# medulla_2026-05-03.net
KiCad netlist of a schematic drawn in EasyEDA Pro
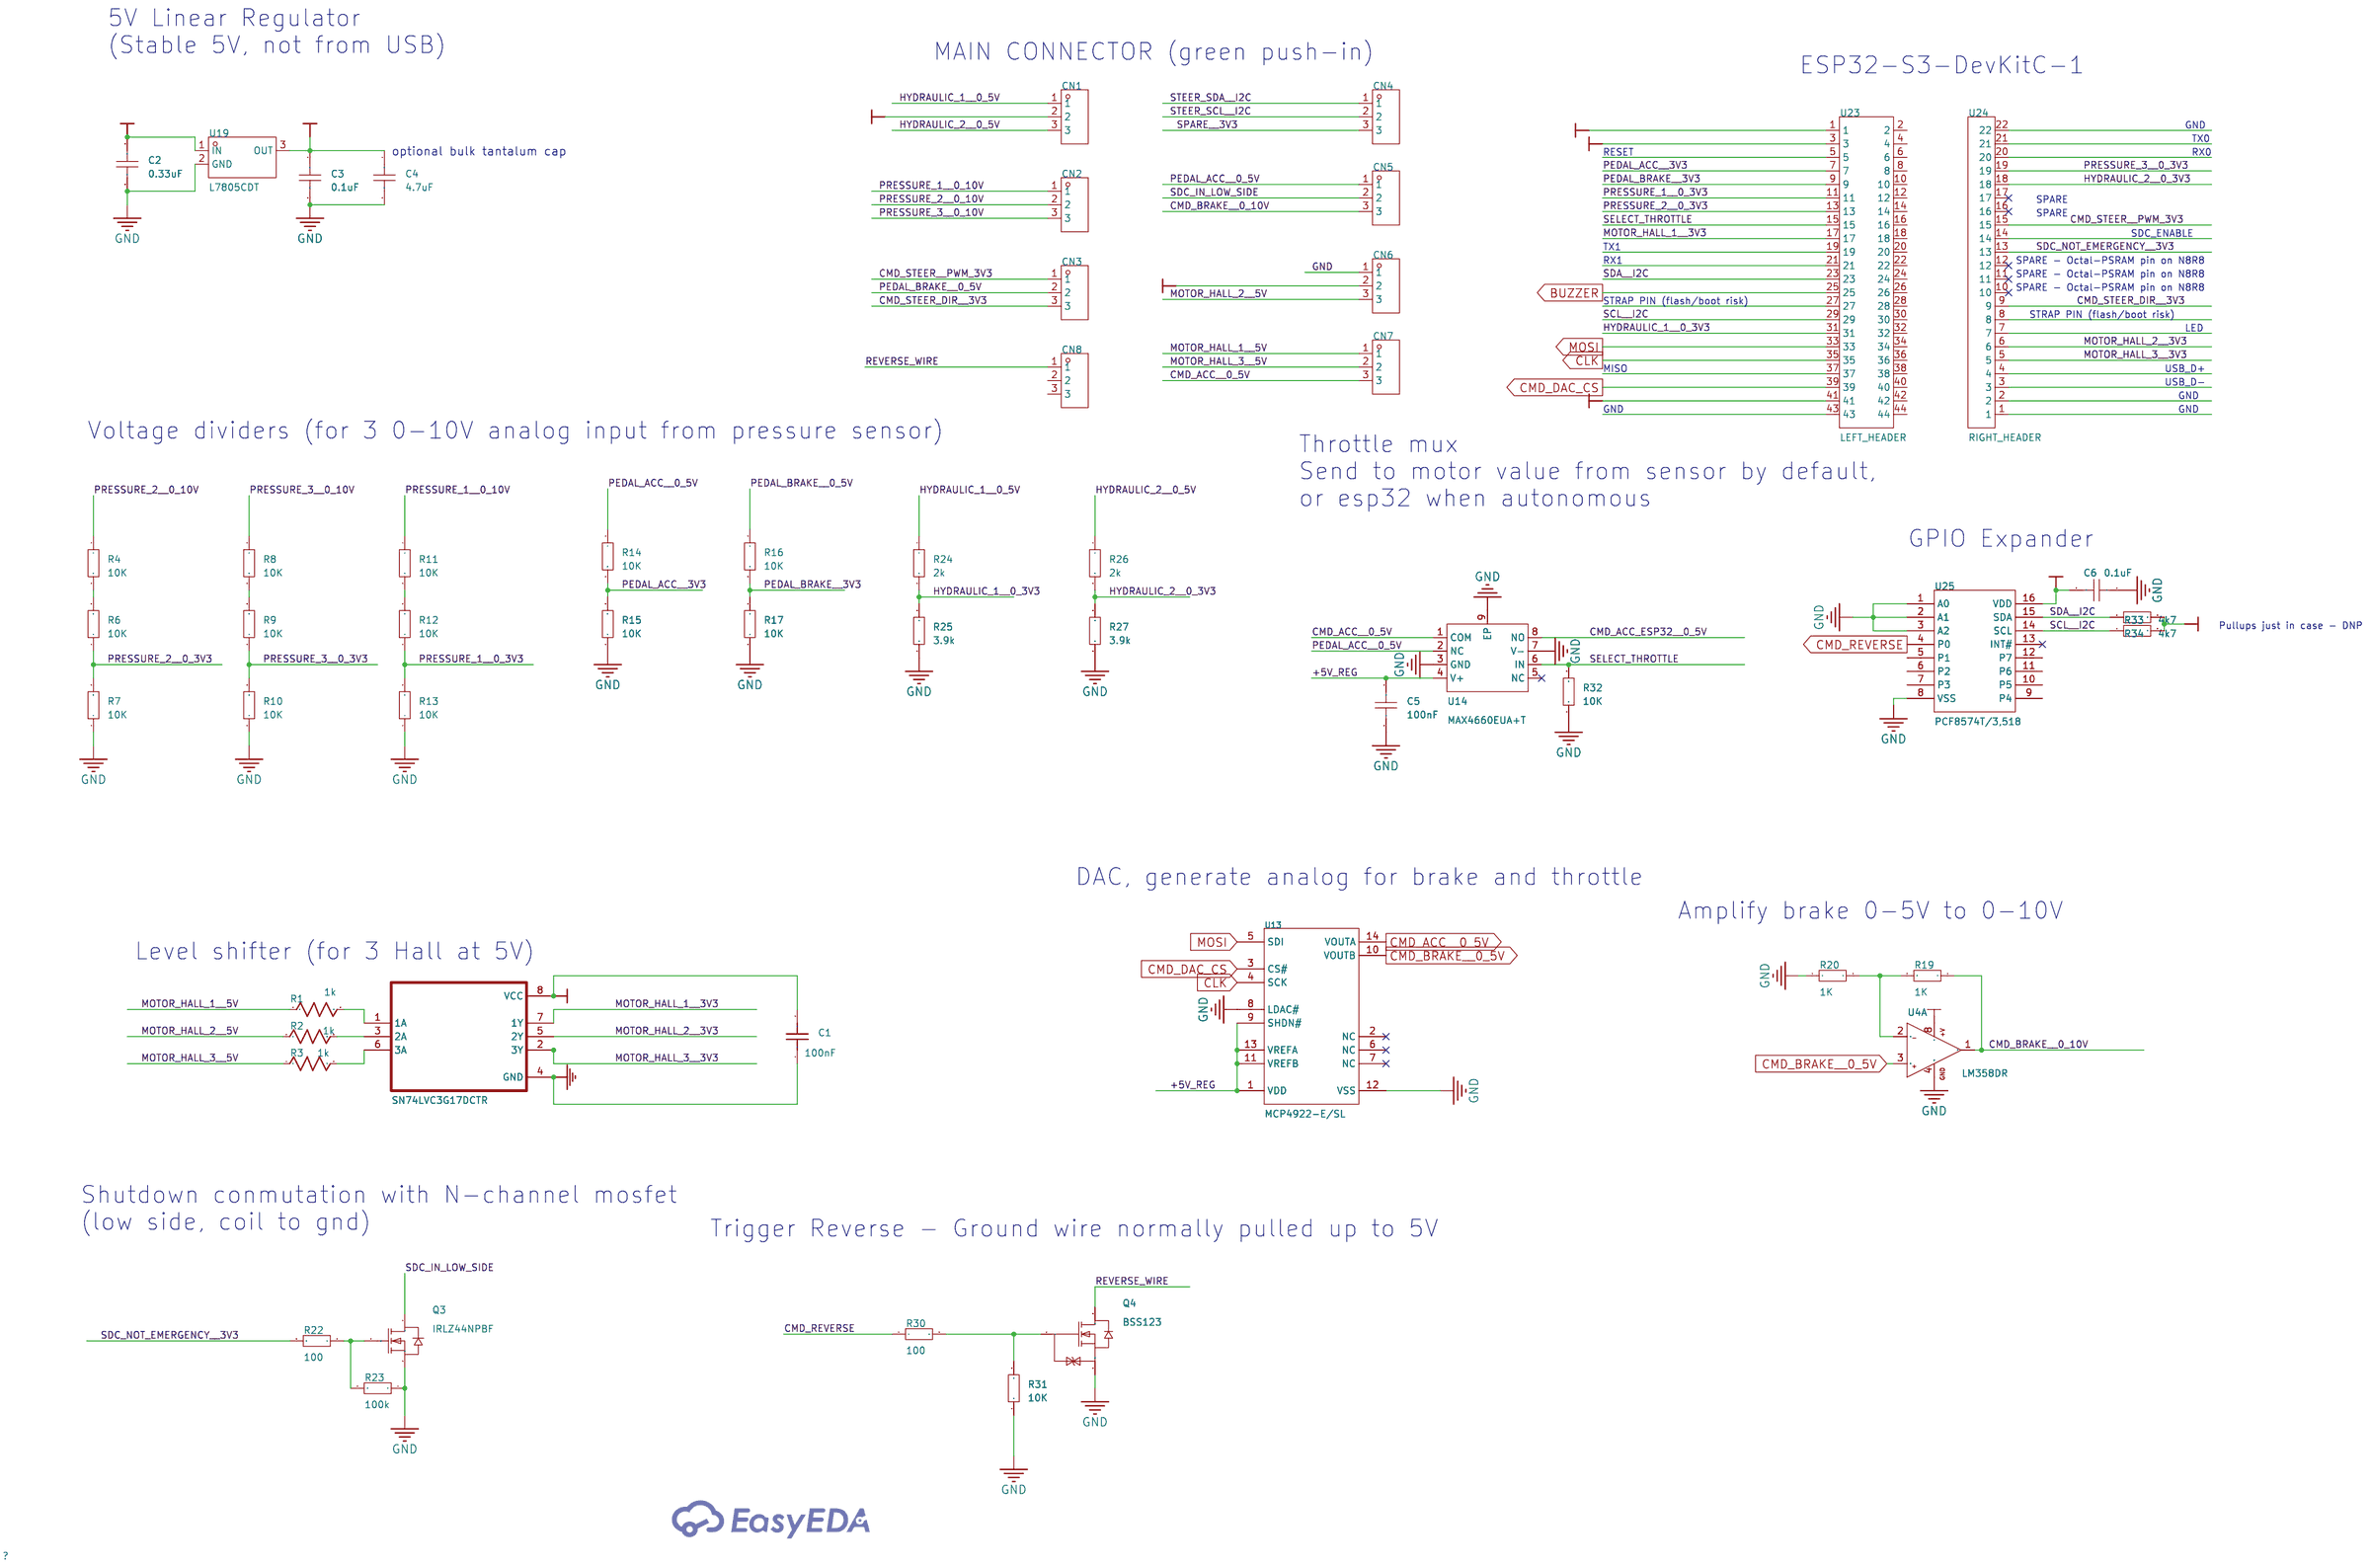
[diagram p0: schematic sheet]

(export (version "E")
  (design (tool "Eeschema 10.0.6"))
  (components
    (comp (ref "C1")
      (value "100nF")
      (footprint "easyedapro:C0603")
      (fields (field (name "Contributor") "LCEDA_Lib"))
      (libsource (lib "easyedapro") (part "100nF"))
    )
    (comp (ref "C2")
      (value "0.33uF")
      (footprint "easyedapro:C0603")
      (libsource (lib "easyedapro") (part "CAP"))
    )
    (comp (ref "C3")
      (value "0.1uF")
      (footprint "easyedapro:C0603")
      (libsource (lib "easyedapro") (part "CAP"))
    )
    (comp (ref "C4")
      (value "4.7uF")
      (footprint "easyedapro:C0603")
      (libsource (lib "easyedapro") (part "CAP"))
    )
    (comp (ref "C5")
      (value "100nF")
      (footprint "easyedapro:C0603")
      (libsource (lib "easyedapro") (part "CAP"))
    )
    (comp (ref "C6")
      (value "0.1uF")
      (footprint "easyedapro:C0603")
      (libsource (lib "easyedapro") (part "CAP"))
    )
    (comp (ref "CN1")
      (value "1990012")
      (footprint "easyedapro:CONN-TH_3P-P2.50-S5.00_1990012")
      (libsource (lib "easyedapro") (part "1990012"))
    )
    (comp (ref "CN2")
      (value "1990012")
      (footprint "easyedapro:CONN-TH_3P-P2.50-S5.00_1990012")
      (libsource (lib "easyedapro") (part "1990012"))
    )
    (comp (ref "CN3")
      (value "1990012")
      (footprint "easyedapro:CONN-TH_3P-P2.50-S5.00_1990012")
      (libsource (lib "easyedapro") (part "1990012"))
    )
    (comp (ref "CN4")
      (value "1990012")
      (footprint "easyedapro:CONN-TH_3P-P2.50-S5.00_1990012")
      (libsource (lib "easyedapro") (part "1990012"))
    )
    (comp (ref "CN5")
      (value "1990012")
      (footprint "easyedapro:CONN-TH_3P-P2.50-S5.00_1990012")
      (libsource (lib "easyedapro") (part "1990012"))
    )
    (comp (ref "CN6")
      (value "1990012")
      (footprint "easyedapro:CONN-TH_3P-P2.50-S5.00_1990012")
      (libsource (lib "easyedapro") (part "1990012"))
    )
    (comp (ref "CN7")
      (value "1990012")
      (footprint "easyedapro:CONN-TH_3P-P2.50-S5.00_1990012")
      (libsource (lib "easyedapro") (part "1990012"))
    )
    (comp (ref "CN8")
      (value "1990012")
      (footprint "easyedapro:CONN-TH_3P-P2.50-S5.00_1990012")
      (libsource (lib "easyedapro") (part "1990012"))
    )
    (comp (ref "Q3")
      (value "IRLZ44NPBF")
      (footprint "easyedapro:TO-220-3_L10.0-W4.5-P2.54-T")
      (fields (field (name "Manufacturer") "Infineon(英飞凌)"))
      (libsource (lib "easyedapro") (part "IRLZ44NPBF"))
    )
    (comp (ref "Q4")
      (value "BSS123")
      (footprint "easyedapro:SOT-23_L2.9-W1.3-P1.90-LS2.4-BR")
      (fields (field (name "Manufacturer") "HXY MOSFET(华轩阳电子)"))
      (libsource (lib "easyedapro") (part "BSS123_C5184436"))
    )
    (comp (ref "R1")
      (value "1k")
      (footprint "easyedapro:R0603")
      (fields (field (name "Contributor") "LCEDA_Lib"))
      (libsource (lib "easyedapro") (part "1k"))
    )
    (comp (ref "R2")
      (value "1k")
      (footprint "easyedapro:R0603")
      (fields (field (name "Contributor") "LCEDA_Lib"))
      (libsource (lib "easyedapro") (part "1k"))
    )
    (comp (ref "R3")
      (value "1k")
      (footprint "easyedapro:R0603")
      (fields (field (name "Contributor") "LCEDA_Lib"))
      (libsource (lib "easyedapro") (part "1k"))
    )
    (comp (ref "R4") (value "10K") (footprint "easyedapro:R0603") (libsource (lib "easyedapro") (part "Res")))
    (comp (ref "R6") (value "10K") (footprint "easyedapro:R0603") (libsource (lib "easyedapro") (part "Res")))
    (comp (ref "R7") (value "10K") (footprint "easyedapro:R0603") (libsource (lib "easyedapro") (part "Res")))
    (comp (ref "R8") (value "10K") (footprint "easyedapro:R0603") (libsource (lib "easyedapro") (part "Res")))
    (comp (ref "R9") (value "10K") (footprint "easyedapro:R0603") (libsource (lib "easyedapro") (part "Res")))
    (comp (ref "R10")
      (value "10K")
      (footprint "easyedapro:R0603")
      (libsource (lib "easyedapro") (part "Res"))
    )
    (comp (ref "R11")
      (value "10K")
      (footprint "easyedapro:R0603")
      (libsource (lib "easyedapro") (part "Res"))
    )
    (comp (ref "R12")
      (value "10K")
      (footprint "easyedapro:R0603")
      (libsource (lib "easyedapro") (part "Res"))
    )
    (comp (ref "R13")
      (value "10K")
      (footprint "easyedapro:R0603")
      (libsource (lib "easyedapro") (part "Res"))
    )
    (comp (ref "R14")
      (value "10K")
      (footprint "easyedapro:R0603")
      (libsource (lib "easyedapro") (part "Res"))
    )
    (comp (ref "R15")
      (value "10K")
      (footprint "easyedapro:R0603")
      (libsource (lib "easyedapro") (part "Res"))
    )
    (comp (ref "R16")
      (value "10K")
      (footprint "easyedapro:R0603")
      (libsource (lib "easyedapro") (part "Res"))
    )
    (comp (ref "R17")
      (value "10K")
      (footprint "easyedapro:R0603")
      (libsource (lib "easyedapro") (part "Res"))
    )
    (comp (ref "R19") (value "1K") (footprint "easyedapro:R0603") (libsource (lib "easyedapro") (part "Res")))
    (comp (ref "R20") (value "1K") (footprint "easyedapro:R0603") (libsource (lib "easyedapro") (part "Res")))
    (comp (ref "R22")
      (value "100")
      (footprint "easyedapro:R0603")
      (libsource (lib "easyedapro") (part "Res"))
    )
    (comp (ref "R23")
      (value "100k")
      (footprint "easyedapro:R0603")
      (libsource (lib "easyedapro") (part "Res"))
    )
    (comp (ref "R24") (value "2k") (footprint "easyedapro:R0603") (libsource (lib "easyedapro") (part "Res")))
    (comp (ref "R25")
      (value "3.9k")
      (footprint "easyedapro:R0603")
      (libsource (lib "easyedapro") (part "Res"))
    )
    (comp (ref "R26") (value "2k") (footprint "easyedapro:R0603") (libsource (lib "easyedapro") (part "Res")))
    (comp (ref "R27")
      (value "3.9k")
      (footprint "easyedapro:R0603")
      (libsource (lib "easyedapro") (part "Res"))
    )
    (comp (ref "R30")
      (value "100")
      (footprint "easyedapro:R0603")
      (libsource (lib "easyedapro") (part "Res"))
    )
    (comp (ref "R31")
      (value "10K")
      (footprint "easyedapro:R0603")
      (libsource (lib "easyedapro") (part "Res"))
    )
    (comp (ref "R32")
      (value "10K")
      (footprint "easyedapro:R0603")
      (libsource (lib "easyedapro") (part "Res"))
    )
    (comp (ref "R33")
      (value "4k7")
      (footprint "easyedapro:R0603")
      (libsource (lib "easyedapro") (part "Res"))
    )
    (comp (ref "R34")
      (value "4k7")
      (footprint "easyedapro:R0603")
      (libsource (lib "easyedapro") (part "Res"))
    )
    (comp (ref "U4")
      (value "LM358DR")
      (footprint "easyedapro:SOIC-8_L5.0-W4.0-P1.27-LS6.0-BL")
      (fields (field (name "Manufacturer") "TI(德州仪器)"))
      (libsource (lib "easyedapro") (part "LM358DR"))
    )
    (comp (ref "U5")
      (value "SN74LVC3G17DCTR")
      (footprint "easyedapro:SOP65P400X130-8N")
      (libsource (lib "easyedapro") (part "SN74LVC3G17DCTR"))
    )
    (comp (ref "U13")
      (value "MCP4922-E/SL")
      (footprint "easyedapro:SOIC-14_L8.7-W3.9-P1.27-LS6.0-BL")
      (fields (field (name "Manufacturer") "MICROCHIP(美国微芯)"))
      (libsource (lib "easyedapro") (part "MCP4922-E/SL"))
    )
    (comp (ref "U14")
      (value "MAX4660EUA+T")
      (footprint "easyedapro:UMAX-8_L3.0-W3.0-P0.65-LS4.9-BL-EP")
      (fields (field (name "Manufacturer") "ADI(亚德诺)/MAXIM(美信)"))
      (libsource (lib "easyedapro") (part "MAX4660EUA+T"))
    )
    (comp (ref "U19")
      (value "L7805CDT")
      (footprint "easyedapro:TO-252-2_L6.6-W6.1-P4.57-LS9.9-BR-CW")
      (fields (field (name "Manufacturer") "HXY MOSFET(华轩阳电子)"))
      (libsource (lib "easyedapro") (part "L7805CDT_C20611927"))
    )
    (comp (ref "U23")
      (value "LEFT_HEADER")
      (footprint "easyedapro:HDR-TH_ESQ-122-59-G-D")
      (fields (field (name "Manufacturer") "SAMTEC"))
      (libsource (lib "easyedapro") (part "SSW-122-01-T-D"))
    )
    (comp (ref "U24")
      (value "RIGHT_HEADER")
      (footprint "easyedapro:HDR-TH_ESQ-122-23-G-S")
      (fields (field (name "Manufacturer") "SAMTEC"))
      (libsource (lib "easyedapro") (part "SSW-122-01-T-S"))
    )
    (comp (ref "U25")
      (value "PCF8574T/3,518")
      (footprint "easyedapro:SOIC-16_L10.3-W7.5-P1.27-LS10.3-BL")
      (fields (field (name "Manufacturer") "NXP(恩智浦)"))
      (libsource (lib "easyedapro") (part "PCF8574T/3,518"))
    )
  )
  (nets
    (net (code "1") (name "+5V_REG") (class "Default")
      (node (ref "C3") (pin "1") (pinfunction "1_1") (pintype "input"))
      (node (ref "C4") (pin "1") (pinfunction "1_1") (pintype "input"))
      (node (ref "C5") (pin "1") (pinfunction "1_1") (pintype "input"))
      (node (ref "U13") (pin "1") (pinfunction "VDD_1") (pintype "input"))
      (node (ref "U13") (pin "11") (pinfunction "VREFB_11") (pintype "input"))
      (node (ref "U13") (pin "13") (pinfunction "VREFA_13") (pintype "input"))
      (node (ref "U13") (pin "9") (pinfunction "SHDN#_9") (pintype "input"))
      (node (ref "U14") (pin "4") (pinfunction "V+_4") (pintype "unspecified"))
      (node (ref "U19") (pin "3") (pinfunction "OUT_3") (pintype "unspecified"))
    )
    (net (code "2") (name "+5V_USB") (class "Default")
      (node (ref "U23") (pin "41") (pinfunction "41_41") (pintype "unspecified"))
    )
    (net (code "3") (name "/CMD_ACC_ESP32__0_5V") (class "Default")
      (node (ref "U14") (pin "8") (pinfunction "NO_8") (pintype "unspecified"))
    )
    (net (code "4") (name "/CMD_BRAKE__0_10V") (class "Default")
      (node (ref "CN5") (pin "3") (pinfunction "3_3") (pintype "unspecified"))
      (node (ref "R19") (pin "1") (pinfunction "1_1") (pintype "input"))
      (node (ref "U4") (pin "1") (pinfunction "OUT1_1") (pintype "output"))
    )
    (net (code "5") (name "/CMD_STEER_DIR__3V3") (class "Default")
      (node (ref "CN3") (pin "3") (pinfunction "3_3") (pintype "unspecified"))
      (node (ref "U24") (pin "9") (pinfunction "9_9") (pintype "unspecified"))
    )
    (net (code "6") (name "/CMD_STEER__PWM_3V3") (class "Default")
      (node (ref "CN3") (pin "1") (pinfunction "1_1") (pintype "unspecified"))
      (node (ref "U24") (pin "15") (pinfunction "15_15") (pintype "unspecified"))
    )
    (net (code "7") (name "/HYDRAULIC_1__0_3V3") (class "Default")
      (node (ref "R24") (pin "2") (pinfunction "2_2") (pintype "input"))
      (node (ref "R25") (pin "2") (pinfunction "2_2") (pintype "input"))
      (node (ref "U23") (pin "31") (pinfunction "31_31") (pintype "unspecified"))
    )
    (net (code "8") (name "/HYDRAULIC_1__0_5V") (class "Default")
      (node (ref "CN1") (pin "1") (pinfunction "1_1") (pintype "unspecified"))
      (node (ref "R24") (pin "1") (pinfunction "1_1") (pintype "input"))
    )
    (net (code "9") (name "/HYDRAULIC_2__0_3V3") (class "Default")
      (node (ref "R26") (pin "2") (pinfunction "2_2") (pintype "input"))
      (node (ref "R27") (pin "2") (pinfunction "2_2") (pintype "input"))
      (node (ref "U24") (pin "18") (pinfunction "18_18") (pintype "unspecified"))
    )
    (net (code "10") (name "/HYDRAULIC_2__0_5V") (class "Default")
      (node (ref "CN1") (pin "3") (pinfunction "3_3") (pintype "unspecified"))
      (node (ref "R26") (pin "1") (pinfunction "1_1") (pintype "input"))
    )
    (net (code "11") (name "/MOTOR_HALL_1__3V3") (class "Default")
      (node (ref "U23") (pin "17") (pinfunction "17_17") (pintype "unspecified"))
      (node (ref "U5") (pin "7") (pinfunction "1Y_7") (pintype "output"))
    )
    (net (code "12") (name "/MOTOR_HALL_1__5V") (class "Default")
      (node (ref "CN7") (pin "1") (pinfunction "1_1") (pintype "unspecified"))
      (node (ref "R1") (pin "1") (pinfunction "1_1") (pintype "unspecified"))
    )
    (net (code "13") (name "/MOTOR_HALL_2__3V3") (class "Default")
      (node (ref "U24") (pin "6") (pinfunction "6_6") (pintype "unspecified"))
      (node (ref "U5") (pin "5") (pinfunction "2Y_5") (pintype "output"))
    )
    (net (code "14") (name "/MOTOR_HALL_2__5V") (class "Default")
      (node (ref "CN6") (pin "3") (pinfunction "3_3") (pintype "unspecified"))
      (node (ref "R2") (pin "1") (pinfunction "1_1") (pintype "unspecified"))
    )
    (net (code "15") (name "/MOTOR_HALL_3__3V3") (class "Default")
      (node (ref "U24") (pin "5") (pinfunction "5_5") (pintype "unspecified"))
      (node (ref "U5") (pin "2") (pinfunction "3Y_2") (pintype "output"))
    )
    (net (code "16") (name "/MOTOR_HALL_3__5V") (class "Default")
      (node (ref "CN7") (pin "2") (pinfunction "2_2") (pintype "unspecified"))
      (node (ref "R3") (pin "1") (pinfunction "1_1") (pintype "unspecified"))
    )
    (net (code "17") (name "/PEDAL_ACC__0_5V") (class "Default")
      (node (ref "CN5") (pin "1") (pinfunction "1_1") (pintype "unspecified"))
      (node (ref "R14") (pin "1") (pinfunction "1_1") (pintype "input"))
      (node (ref "U14") (pin "2") (pinfunction "NC_2") (pintype "unspecified"))
    )
    (net (code "18") (name "/PEDAL_ACC__3V3") (class "Default")
      (node (ref "R14") (pin "2") (pinfunction "2_2") (pintype "input"))
      (node (ref "R15") (pin "2") (pinfunction "2_2") (pintype "input"))
      (node (ref "U23") (pin "7") (pinfunction "7_7") (pintype "unspecified"))
    )
    (net (code "19") (name "/PEDAL_BRAKE__0_5V") (class "Default")
      (node (ref "CN3") (pin "2") (pinfunction "2_2") (pintype "unspecified"))
      (node (ref "R16") (pin "1") (pinfunction "1_1") (pintype "input"))
    )
    (net (code "20") (name "/PEDAL_BRAKE__3V3") (class "Default")
      (node (ref "R16") (pin "2") (pinfunction "2_2") (pintype "input"))
      (node (ref "R17") (pin "2") (pinfunction "2_2") (pintype "input"))
      (node (ref "U23") (pin "9") (pinfunction "9_9") (pintype "unspecified"))
    )
    (net (code "21") (name "/PRESSURE_1__0_3V3") (class "Default")
      (node (ref "R12") (pin "1") (pinfunction "1_1") (pintype "input"))
      (node (ref "R13") (pin "2") (pinfunction "2_2") (pintype "input"))
      (node (ref "U23") (pin "11") (pinfunction "11_11") (pintype "unspecified"))
    )
    (net (code "22") (name "/PRESSURE_1__0_10V") (class "Default")
      (node (ref "CN2") (pin "1") (pinfunction "1_1") (pintype "unspecified"))
      (node (ref "R11") (pin "1") (pinfunction "1_1") (pintype "input"))
    )
    (net (code "23") (name "/PRESSURE_2__0_3V3") (class "Default")
      (node (ref "R6") (pin "1") (pinfunction "1_1") (pintype "input"))
      (node (ref "R7") (pin "2") (pinfunction "2_2") (pintype "input"))
      (node (ref "U23") (pin "13") (pinfunction "13_13") (pintype "unspecified"))
    )
    (net (code "24") (name "/PRESSURE_2__0_10V") (class "Default")
      (node (ref "CN2") (pin "2") (pinfunction "2_2") (pintype "unspecified"))
      (node (ref "R4") (pin "1") (pinfunction "1_1") (pintype "input"))
    )
    (net (code "25") (name "/PRESSURE_3__0_3V3") (class "Default")
      (node (ref "R10") (pin "2") (pinfunction "2_2") (pintype "input"))
      (node (ref "R9") (pin "1") (pinfunction "1_1") (pintype "input"))
      (node (ref "U24") (pin "19") (pinfunction "19_19") (pintype "unspecified"))
    )
    (net (code "26") (name "/PRESSURE_3__0_10V") (class "Default")
      (node (ref "CN2") (pin "3") (pinfunction "3_3") (pintype "unspecified"))
      (node (ref "R8") (pin "1") (pinfunction "1_1") (pintype "input"))
    )
    (net (code "27") (name "/REVERSE_WIRE") (class "Default")
      (node (ref "CN8") (pin "1") (pinfunction "1_1") (pintype "unspecified"))
      (node (ref "Q4") (pin "3") (pinfunction "D_3") (pintype "unspecified"))
    )
    (net (code "28") (name "/SCL__I2C") (class "Default")
      (node (ref "R34") (pin "1") (pinfunction "1_1") (pintype "input"))
      (node (ref "U23") (pin "29") (pinfunction "29_29") (pintype "unspecified"))
      (node (ref "U25") (pin "14") (pinfunction "SCL_14") (pintype "unspecified"))
    )
    (net (code "29") (name "/SDA__I2C") (class "Default")
      (node (ref "R33") (pin "1") (pinfunction "1_1") (pintype "input"))
      (node (ref "U23") (pin "23") (pinfunction "23_23") (pintype "unspecified"))
      (node (ref "U25") (pin "15") (pinfunction "SDA_15") (pintype "unspecified"))
    )
    (net (code "30") (name "/SDC_IN_LOW_SIDE") (class "Default")
      (node (ref "CN5") (pin "2") (pinfunction "2_2") (pintype "unspecified"))
      (node (ref "Q3") (pin "2") (pinfunction "D_2") (pintype "unspecified"))
    )
    (net (code "31") (name "/SDC_NOT_EMERGENCY__3V3") (class "Default")
      (node (ref "R22") (pin "2") (pinfunction "2_2") (pintype "input"))
      (node (ref "U24") (pin "13") (pinfunction "13_13") (pintype "unspecified"))
    )
    (net (code "32") (name "/SELECT_THROTTLE") (class "Default")
      (node (ref "R32") (pin "2") (pinfunction "2_2") (pintype "input"))
      (node (ref "U14") (pin "6") (pinfunction "IN_6") (pintype "unspecified"))
      (node (ref "U23") (pin "15") (pinfunction "15_15") (pintype "unspecified"))
    )
    (net (code "33") (name "/SPARE__3V3") (class "Default")
      (node (ref "CN4") (pin "3") (pinfunction "3_3") (pintype "unspecified"))
    )
    (net (code "34") (name "/STEER_SCL__I2C") (class "Default")
      (node (ref "CN4") (pin "2") (pinfunction "2_2") (pintype "unspecified"))
    )
    (net (code "35") (name "/STEER_SDA__I2C") (class "Default")
      (node (ref "CN4") (pin "1") (pinfunction "1_1") (pintype "unspecified"))
    )
    (net (code "36") (name "3V3") (class "Default")
      (node (ref "C1") (pin "2") (pinfunction "2_2") (pintype "unspecified"))
      (node (ref "C6") (pin "2") (pinfunction "2_2") (pintype "input"))
      (node (ref "CN1") (pin "2") (pinfunction "2_2") (pintype "unspecified"))
      (node (ref "R33") (pin "2") (pinfunction "2_2") (pintype "input"))
      (node (ref "R34") (pin "2") (pinfunction "2_2") (pintype "input"))
      (node (ref "U23") (pin "1") (pinfunction "1_1") (pintype "unspecified"))
      (node (ref "U23") (pin "3") (pinfunction "3_3") (pintype "unspecified"))
      (node (ref "U25") (pin "16") (pinfunction "VDD_16") (pintype "unspecified"))
      (node (ref "U5") (pin "8") (pinfunction "VCC_8") (pintype "unspecified"))
    )
    (net (code "37") (name "12V") (class "Default")
      (node (ref "C2") (pin "1") (pinfunction "1_1") (pintype "input"))
      (node (ref "CN6") (pin "2") (pinfunction "2_2") (pintype "unspecified"))
      (node (ref "U19") (pin "1") (pinfunction "IN_1") (pintype "unspecified"))
      (node (ref "U4") (pin "8") (pinfunction "+V_8") (pintype "unspecified"))
    )
    (net (code "38") (name "BUZZER") (class "Default")
      (node (ref "U23") (pin "25") (pinfunction "25_25") (pintype "unspecified"))
    )
    (net (code "39") (name "CLK") (class "Default")
      (node (ref "U13") (pin "4") (pinfunction "SCK_4") (pintype "input"))
      (node (ref "U23") (pin "35") (pinfunction "35_35") (pintype "unspecified"))
    )
    (net (code "40") (name "CMD_ACC__0_5V") (class "Default")
      (node (ref "CN7") (pin "3") (pinfunction "3_3") (pintype "unspecified"))
      (node (ref "U13") (pin "14") (pinfunction "VOUTA_14") (pintype "output"))
      (node (ref "U14") (pin "1") (pinfunction "COM_1") (pintype "unspecified"))
    )
    (net (code "41") (name "CMD_BRAKE__0_5V") (class "Default")
      (node (ref "U13") (pin "10") (pinfunction "VOUTB_10") (pintype "output"))
      (node (ref "U4") (pin "3") (pinfunction "+IN1_3") (pintype "input"))
    )
    (net (code "42") (name "CMD_DAC_CS") (class "Default")
      (node (ref "U13") (pin "3") (pinfunction "CS#_3") (pintype "input"))
      (node (ref "U23") (pin "39") (pinfunction "39_39") (pintype "unspecified"))
    )
    (net (code "43") (name "CMD_REVERSE") (class "Default")
      (node (ref "R30") (pin "1") (pinfunction "1_1") (pintype "input"))
      (node (ref "U25") (pin "4") (pinfunction "P0_4") (pintype "unspecified"))
    )
    (net (code "44") (name "GND") (class "Default")
      (node (ref "C1") (pin "1") (pinfunction "1_1") (pintype "unspecified"))
      (node (ref "C2") (pin "2") (pinfunction "2_2") (pintype "input"))
      (node (ref "C3") (pin "2") (pinfunction "2_2") (pintype "input"))
      (node (ref "C4") (pin "2") (pinfunction "2_2") (pintype "input"))
      (node (ref "C5") (pin "2") (pinfunction "2_2") (pintype "input"))
      (node (ref "C6") (pin "1") (pinfunction "1_1") (pintype "input"))
      (node (ref "CN6") (pin "1") (pinfunction "1_1") (pintype "unspecified"))
      (node (ref "Q3") (pin "3") (pinfunction "S_3") (pintype "unspecified"))
      (node (ref "Q4") (pin "2") (pinfunction "S_2") (pintype "unspecified"))
      (node (ref "R10") (pin "1") (pinfunction "1_1") (pintype "input"))
      (node (ref "R13") (pin "1") (pinfunction "1_1") (pintype "input"))
      (node (ref "R15") (pin "1") (pinfunction "1_1") (pintype "input"))
      (node (ref "R17") (pin "1") (pinfunction "1_1") (pintype "input"))
      (node (ref "R20") (pin "1") (pinfunction "1_1") (pintype "input"))
      (node (ref "R23") (pin "1") (pinfunction "1_1") (pintype "input"))
      (node (ref "R25") (pin "1") (pinfunction "1_1") (pintype "input"))
      (node (ref "R27") (pin "1") (pinfunction "1_1") (pintype "input"))
      (node (ref "R31") (pin "1") (pinfunction "1_1") (pintype "input"))
      (node (ref "R32") (pin "1") (pinfunction "1_1") (pintype "input"))
      (node (ref "R7") (pin "1") (pinfunction "1_1") (pintype "input"))
      (node (ref "U13") (pin "12") (pinfunction "VSS_12") (pintype "input"))
      (node (ref "U13") (pin "8") (pinfunction "LDAC#_8") (pintype "input"))
      (node (ref "U14") (pin "3") (pinfunction "GND_3") (pintype "unspecified"))
      (node (ref "U14") (pin "7") (pinfunction "V-_7") (pintype "unspecified"))
      (node (ref "U14") (pin "9") (pinfunction "EP_9") (pintype "unspecified"))
      (node (ref "U19") (pin "2") (pinfunction "GND_2") (pintype "unspecified"))
      (node (ref "U25") (pin "1") (pinfunction "A0_1") (pintype "unspecified"))
      (node (ref "U25") (pin "2") (pinfunction "A1_2") (pintype "unspecified"))
      (node (ref "U25") (pin "3") (pinfunction "A2_3") (pintype "unspecified"))
      (node (ref "U25") (pin "8") (pinfunction "VSS_8") (pintype "unspecified"))
      (node (ref "U4") (pin "4") (pinfunction "GND_4") (pintype "unspecified"))
      (node (ref "U5") (pin "4") (pinfunction "GND_4") (pintype "unspecified"))
    )
    (net (code "45") (name "MOSI") (class "Default")
      (node (ref "U13") (pin "5") (pinfunction "SDI_5") (pintype "input"))
      (node (ref "U23") (pin "33") (pinfunction "33_33") (pintype "unspecified"))
    )
    (net (code "46") (name "Net-(Q3-G)") (class "Default")
      (node (ref "Q3") (pin "1") (pinfunction "G_1") (pintype "unspecified"))
      (node (ref "R22") (pin "1") (pinfunction "1_1") (pintype "input"))
      (node (ref "R23") (pin "2") (pinfunction "2_2") (pintype "input"))
    )
    (net (code "47") (name "Net-(Q4-G)") (class "Default")
      (node (ref "Q4") (pin "1") (pinfunction "G_1") (pintype "unspecified"))
      (node (ref "R30") (pin "2") (pinfunction "2_2") (pintype "input"))
      (node (ref "R31") (pin "2") (pinfunction "2_2") (pintype "input"))
    )
    (net (code "48") (name "Net-(R4-Pad2)") (class "Default")
      (node (ref "R4") (pin "2") (pinfunction "2_2") (pintype "input"))
      (node (ref "R6") (pin "2") (pinfunction "2_2") (pintype "input"))
    )
    (net (code "49") (name "Net-(R8-Pad2)") (class "Default")
      (node (ref "R8") (pin "2") (pinfunction "2_2") (pintype "input"))
      (node (ref "R9") (pin "2") (pinfunction "2_2") (pintype "input"))
    )
    (net (code "50") (name "Net-(R11-Pad2)") (class "Default")
      (node (ref "R11") (pin "2") (pinfunction "2_2") (pintype "input"))
      (node (ref "R12") (pin "2") (pinfunction "2_2") (pintype "input"))
    )
    (net (code "51") (name "Net-(U4A--IN1)") (class "Default")
      (node (ref "R19") (pin "2") (pinfunction "2_2") (pintype "input"))
      (node (ref "R20") (pin "2") (pinfunction "2_2") (pintype "input"))
      (node (ref "U4") (pin "2") (pinfunction "-IN1_2") (pintype "input"))
    )
    (net (code "52") (name "Net-(U5-1A)") (class "Default")
      (node (ref "R1") (pin "2") (pinfunction "2_2") (pintype "unspecified"))
      (node (ref "U5") (pin "1") (pinfunction "1A_1") (pintype "input"))
    )
    (net (code "53") (name "Net-(U5-2A)") (class "Default")
      (node (ref "R2") (pin "2") (pinfunction "2_2") (pintype "unspecified"))
      (node (ref "U5") (pin "3") (pinfunction "2A_3") (pintype "input"))
    )
    (net (code "54") (name "Net-(U5-3A)") (class "Default")
      (node (ref "R3") (pin "2") (pinfunction "2_2") (pintype "unspecified"))
      (node (ref "U5") (pin "6") (pinfunction "3A_6") (pintype "input"))
    )
    (net (code "55") (name "unconnected-(CN8-Pad2)") (class "Default")
      (node (ref "CN8") (pin "2") (pinfunction "2_2") (pintype "unspecified"))
    )
    (net (code "56") (name "unconnected-(CN8-Pad3)") (class "Default")
      (node (ref "CN8") (pin "3") (pinfunction "3_3") (pintype "unspecified"))
    )
    (net (code "57") (name "unconnected-(U13-NC-Pad2)") (class "Default")
      (node (ref "U13") (pin "2") (pinfunction "NC_2") (pintype "input+no_connect"))
    )
    (net (code "58") (name "unconnected-(U13-NC-Pad6)") (class "Default")
      (node (ref "U13") (pin "6") (pinfunction "NC_6") (pintype "input+no_connect"))
    )
    (net (code "59") (name "unconnected-(U13-NC-Pad7)") (class "Default")
      (node (ref "U13") (pin "7") (pinfunction "NC_7") (pintype "input+no_connect"))
    )
    (net (code "60") (name "unconnected-(U14-NC-Pad5)") (class "Default")
      (node (ref "U14") (pin "5") (pinfunction "NC_5") (pintype "unspecified+no_connect"))
    )
    (net (code "61") (name "unconnected-(U23-Pad2)") (class "Default")
      (node (ref "U23") (pin "2") (pinfunction "2_2") (pintype "unspecified"))
    )
    (net (code "62") (name "unconnected-(U23-Pad4)") (class "Default")
      (node (ref "U23") (pin "4") (pinfunction "4_4") (pintype "unspecified"))
    )
    (net (code "63") (name "unconnected-(U23-Pad5)") (class "Default")
      (node (ref "U23") (pin "5") (pinfunction "5_5") (pintype "unspecified"))
    )
    (net (code "64") (name "unconnected-(U23-Pad6)") (class "Default")
      (node (ref "U23") (pin "6") (pinfunction "6_6") (pintype "unspecified"))
    )
    (net (code "65") (name "unconnected-(U23-Pad8)") (class "Default")
      (node (ref "U23") (pin "8") (pinfunction "8_8") (pintype "unspecified"))
    )
    (net (code "66") (name "unconnected-(U23-Pad10)") (class "Default")
      (node (ref "U23") (pin "10") (pinfunction "10_10") (pintype "unspecified"))
    )
    (net (code "67") (name "unconnected-(U23-Pad12)") (class "Default")
      (node (ref "U23") (pin "12") (pinfunction "12_12") (pintype "unspecified"))
    )
    (net (code "68") (name "unconnected-(U23-Pad14)") (class "Default")
      (node (ref "U23") (pin "14") (pinfunction "14_14") (pintype "unspecified"))
    )
    (net (code "69") (name "unconnected-(U23-Pad16)") (class "Default")
      (node (ref "U23") (pin "16") (pinfunction "16_16") (pintype "unspecified"))
    )
    (net (code "70") (name "unconnected-(U23-Pad18)") (class "Default")
      (node (ref "U23") (pin "18") (pinfunction "18_18") (pintype "unspecified"))
    )
    (net (code "71") (name "unconnected-(U23-Pad19)") (class "Default")
      (node (ref "U23") (pin "19") (pinfunction "19_19") (pintype "unspecified"))
    )
    (net (code "72") (name "unconnected-(U23-Pad20)") (class "Default")
      (node (ref "U23") (pin "20") (pinfunction "20_20") (pintype "unspecified"))
    )
    (net (code "73") (name "unconnected-(U23-Pad21)") (class "Default")
      (node (ref "U23") (pin "21") (pinfunction "21_21") (pintype "unspecified"))
    )
    (net (code "74") (name "unconnected-(U23-Pad22)") (class "Default")
      (node (ref "U23") (pin "22") (pinfunction "22_22") (pintype "unspecified"))
    )
    (net (code "75") (name "unconnected-(U23-Pad24)") (class "Default")
      (node (ref "U23") (pin "24") (pinfunction "24_24") (pintype "unspecified"))
    )
    (net (code "76") (name "unconnected-(U23-Pad26)") (class "Default")
      (node (ref "U23") (pin "26") (pinfunction "26_26") (pintype "unspecified"))
    )
    (net (code "77") (name "unconnected-(U23-Pad27)") (class "Default")
      (node (ref "U23") (pin "27") (pinfunction "27_27") (pintype "unspecified"))
    )
    (net (code "78") (name "unconnected-(U23-Pad28)") (class "Default")
      (node (ref "U23") (pin "28") (pinfunction "28_28") (pintype "unspecified"))
    )
    (net (code "79") (name "unconnected-(U23-Pad30)") (class "Default")
      (node (ref "U23") (pin "30") (pinfunction "30_30") (pintype "unspecified"))
    )
    (net (code "80") (name "unconnected-(U23-Pad32)") (class "Default")
      (node (ref "U23") (pin "32") (pinfunction "32_32") (pintype "unspecified"))
    )
    (net (code "81") (name "unconnected-(U23-Pad34)") (class "Default")
      (node (ref "U23") (pin "34") (pinfunction "34_34") (pintype "unspecified"))
    )
    (net (code "82") (name "unconnected-(U23-Pad36)") (class "Default")
      (node (ref "U23") (pin "36") (pinfunction "36_36") (pintype "unspecified"))
    )
    (net (code "83") (name "unconnected-(U23-Pad37)") (class "Default")
      (node (ref "U23") (pin "37") (pinfunction "37_37") (pintype "unspecified"))
    )
    (net (code "84") (name "unconnected-(U23-Pad38)") (class "Default")
      (node (ref "U23") (pin "38") (pinfunction "38_38") (pintype "unspecified"))
    )
    (net (code "85") (name "unconnected-(U23-Pad40)") (class "Default")
      (node (ref "U23") (pin "40") (pinfunction "40_40") (pintype "unspecified"))
    )
    (net (code "86") (name "unconnected-(U23-Pad42)") (class "Default")
      (node (ref "U23") (pin "42") (pinfunction "42_42") (pintype "unspecified"))
    )
    (net (code "87") (name "unconnected-(U23-Pad43)") (class "Default")
      (node (ref "U23") (pin "43") (pinfunction "43_43") (pintype "unspecified"))
    )
    (net (code "88") (name "unconnected-(U23-Pad44)") (class "Default")
      (node (ref "U23") (pin "44") (pinfunction "44_44") (pintype "unspecified"))
    )
    (net (code "89") (name "unconnected-(U24-Pad1)") (class "Default")
      (node (ref "U24") (pin "1") (pinfunction "1_1") (pintype "unspecified"))
    )
    (net (code "90") (name "unconnected-(U24-Pad2)") (class "Default")
      (node (ref "U24") (pin "2") (pinfunction "2_2") (pintype "unspecified"))
    )
    (net (code "91") (name "unconnected-(U24-Pad3)") (class "Default")
      (node (ref "U24") (pin "3") (pinfunction "3_3") (pintype "unspecified"))
    )
    (net (code "92") (name "unconnected-(U24-Pad4)") (class "Default")
      (node (ref "U24") (pin "4") (pinfunction "4_4") (pintype "unspecified"))
    )
    (net (code "93") (name "unconnected-(U24-Pad7)") (class "Default")
      (node (ref "U24") (pin "7") (pinfunction "7_7") (pintype "unspecified"))
    )
    (net (code "94") (name "unconnected-(U24-Pad8)") (class "Default")
      (node (ref "U24") (pin "8") (pinfunction "8_8") (pintype "unspecified"))
    )
    (net (code "95") (name "unconnected-(U24-Pad10)") (class "Default")
      (node (ref "U24") (pin "10") (pinfunction "10_10") (pintype "unspecified+no_connect"))
    )
    (net (code "96") (name "unconnected-(U24-Pad11)") (class "Default")
      (node (ref "U24") (pin "11") (pinfunction "11_11") (pintype "unspecified+no_connect"))
    )
    (net (code "97") (name "unconnected-(U24-Pad12)") (class "Default")
      (node (ref "U24") (pin "12") (pinfunction "12_12") (pintype "unspecified+no_connect"))
    )
    (net (code "98") (name "unconnected-(U24-Pad14)") (class "Default")
      (node (ref "U24") (pin "14") (pinfunction "14_14") (pintype "unspecified"))
    )
    (net (code "99") (name "unconnected-(U24-Pad16)") (class "Default")
      (node (ref "U24") (pin "16") (pinfunction "16_16") (pintype "unspecified+no_connect"))
    )
    (net (code "100") (name "unconnected-(U24-Pad17)") (class "Default")
      (node (ref "U24") (pin "17") (pinfunction "17_17") (pintype "unspecified+no_connect"))
    )
    (net (code "101") (name "unconnected-(U24-Pad20)") (class "Default")
      (node (ref "U24") (pin "20") (pinfunction "20_20") (pintype "unspecified"))
    )
    (net (code "102") (name "unconnected-(U24-Pad21)") (class "Default")
      (node (ref "U24") (pin "21") (pinfunction "21_21") (pintype "unspecified"))
    )
    (net (code "103") (name "unconnected-(U24-Pad22)") (class "Default")
      (node (ref "U24") (pin "22") (pinfunction "22_22") (pintype "unspecified"))
    )
    (net (code "104") (name "unconnected-(U25-INT#-Pad13)") (class "Default")
      (node (ref "U25") (pin "13") (pinfunction "INT#_13") (pintype "unspecified+no_connect"))
    )
    (net (code "105") (name "unconnected-(U25-P1-Pad5)") (class "Default")
      (node (ref "U25") (pin "5") (pinfunction "P1_5") (pintype "unspecified"))
    )
    (net (code "106") (name "unconnected-(U25-P2-Pad6)") (class "Default")
      (node (ref "U25") (pin "6") (pinfunction "P2_6") (pintype "unspecified"))
    )
    (net (code "107") (name "unconnected-(U25-P3-Pad7)") (class "Default")
      (node (ref "U25") (pin "7") (pinfunction "P3_7") (pintype "unspecified"))
    )
    (net (code "108") (name "unconnected-(U25-P4-Pad9)") (class "Default")
      (node (ref "U25") (pin "9") (pinfunction "P4_9") (pintype "unspecified"))
    )
    (net (code "109") (name "unconnected-(U25-P5-Pad10)") (class "Default")
      (node (ref "U25") (pin "10") (pinfunction "P5_10") (pintype "unspecified"))
    )
    (net (code "110") (name "unconnected-(U25-P6-Pad11)") (class "Default")
      (node (ref "U25") (pin "11") (pinfunction "P6_11") (pintype "unspecified"))
    )
    (net (code "111") (name "unconnected-(U25-P7-Pad12)") (class "Default")
      (node (ref "U25") (pin "12") (pinfunction "P7_12") (pintype "unspecified"))
    )
  )
)
